# esp8266_network_speaker.net
KiCad netlist of a schematic drawn in EAGLE
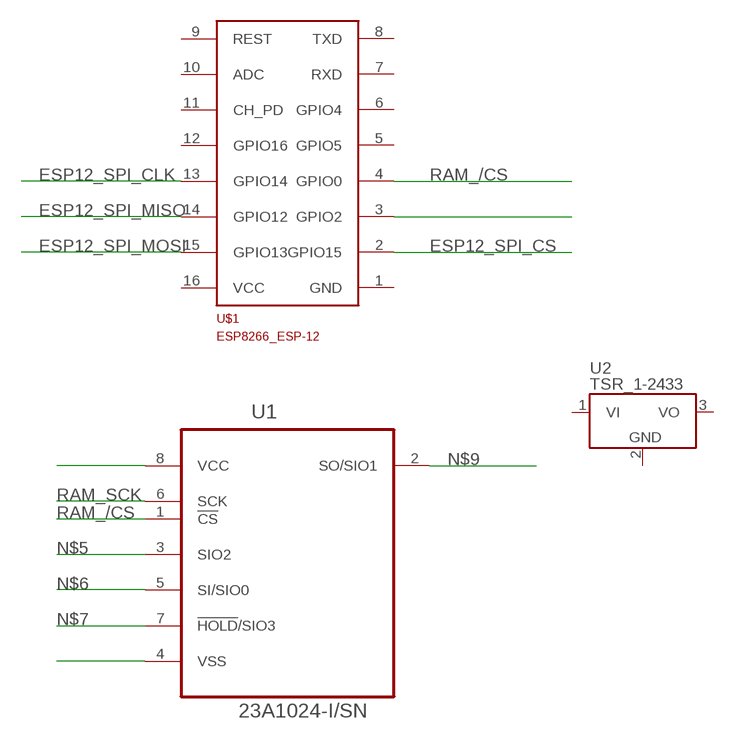
[diagram p0: schematic, sheet 1]

(export (version "E")
  (design (tool "Eeschema 10.0.6"))
  (components
    (comp (ref "U$1")
      (value "ESP8266_ESP-12")
      (footprint "eagle-import:ESP8266-ESP12")
      (libsource (lib "eagle-import") (part "ESP8266_ESP-12"))
    )
    (comp (ref "U1")
      (value "23A1024-I/SN")
      (footprint "eagle-import:SOIC127P600X175-8N")
      (libsource (lib "eagle-import") (part "23A1024-I/SN"))
    )
    (comp (ref "U2")
      (value "TSR_1-2433")
      (footprint "eagle-import:TSR-1")
      (libsource (lib "eagle-import") (part "TSR_1-2433"))
    )
  )
  (nets
    (net (code "1") (name "/ESP12_SPI_CLK") (class "Default")
      (node (ref "U$1") (pin "13") (pinfunction "GPIO14_13") (pintype "bidirectional"))
    )
    (net (code "2") (name "/ESP12_SPI_CS") (class "Default")
      (node (ref "U$1") (pin "2") (pinfunction "GPIO15_2") (pintype "bidirectional"))
    )
    (net (code "3") (name "/ESP12_SPI_MISO") (class "Default")
      (node (ref "U$1") (pin "14") (pinfunction "GPIO12_14") (pintype "bidirectional"))
    )
    (net (code "4") (name "/ESP12_SPI_MOSI") (class "Default")
      (node (ref "U$1") (pin "15") (pinfunction "GPIO13_15") (pintype "bidirectional"))
    )
    (net (code "5") (name "/GND") (class "Default")
      (node (ref "U2") (pin "2") (pinfunction "GND_2") (pintype "power_in"))
    )
    (net (code "6") (name "/N$5") (class "Default")
      (node (ref "U1") (pin "3") (pinfunction "SIO2_3") (pintype "passive"))
    )
    (net (code "7") (name "/N$6") (class "Default")
      (node (ref "U1") (pin "5") (pinfunction "SI/SIO0_5") (pintype "input"))
    )
    (net (code "8") (name "/N$7") (class "Default")
      (node (ref "U1") (pin "7") (pinfunction "~{HOLD}/SIO3_7") (pintype "passive"))
    )
    (net (code "9") (name "/N$9") (class "Default")
      (node (ref "U1") (pin "2") (pinfunction "SO/SIO1_2") (pintype "output"))
    )
    (net (code "10") (name "/RAM_SCK") (class "Default")
      (node (ref "U1") (pin "6") (pinfunction "SCK_6") (pintype "input"))
    )
    (net (code "11") (name "/RAM_{slash}CS") (class "Default")
      (node (ref "U$1") (pin "4") (pinfunction "GPIO0_4") (pintype "bidirectional"))
      (node (ref "U1") (pin "1") (pinfunction "~{CS}_1") (pintype "input"))
    )
    (net (code "12") (name "/VI") (class "Default")
      (node (ref "U2") (pin "1") (pinfunction "VI_1") (pintype "power_in"))
    )
    (net (code "13") (name "/VO") (class "Default")
      (node (ref "U2") (pin "3") (pinfunction "VO_3") (pintype "power_in"))
    )
    (net (code "14") (name "unconnected-(U$1-ADC-Pad10)") (class "Default")
      (node (ref "U$1") (pin "10") (pinfunction "ADC_10") (pintype "bidirectional"))
    )
    (net (code "15") (name "unconnected-(U$1-CH_PD-Pad11)") (class "Default")
      (node (ref "U$1") (pin "11") (pinfunction "CH_PD_11") (pintype "bidirectional"))
    )
    (net (code "16") (name "unconnected-(U$1-GND-Pad1)") (class "Default")
      (node (ref "U$1") (pin "1") (pinfunction "GND_1") (pintype "bidirectional"))
    )
    (net (code "17") (name "unconnected-(U$1-GPIO2-Pad3)") (class "Default")
      (node (ref "U$1") (pin "3") (pinfunction "GPIO2_3") (pintype "bidirectional"))
    )
    (net (code "18") (name "unconnected-(U$1-GPIO4-Pad6)") (class "Default")
      (node (ref "U$1") (pin "6") (pinfunction "GPIO4_6") (pintype "bidirectional"))
    )
    (net (code "19") (name "unconnected-(U$1-GPIO5-Pad5)") (class "Default")
      (node (ref "U$1") (pin "5") (pinfunction "GPIO5_5") (pintype "bidirectional"))
    )
    (net (code "20") (name "unconnected-(U$1-GPIO16-Pad12)") (class "Default")
      (node (ref "U$1") (pin "12") (pinfunction "GPIO16_12") (pintype "bidirectional"))
    )
    (net (code "21") (name "unconnected-(U$1-REST-Pad9)") (class "Default")
      (node (ref "U$1") (pin "9") (pinfunction "REST_9") (pintype "bidirectional"))
    )
    (net (code "22") (name "unconnected-(U$1-RXD-Pad7)") (class "Default")
      (node (ref "U$1") (pin "7") (pinfunction "RXD_7") (pintype "bidirectional"))
    )
    (net (code "23") (name "unconnected-(U$1-TXD-Pad8)") (class "Default")
      (node (ref "U$1") (pin "8") (pinfunction "TXD_8") (pintype "bidirectional"))
    )
    (net (code "24") (name "unconnected-(U$1-VCC-Pad16)") (class "Default")
      (node (ref "U$1") (pin "16") (pinfunction "VCC_16") (pintype "bidirectional"))
    )
    (net (code "25") (name "unconnected-(U1-VCC-Pad8)") (class "Default")
      (node (ref "U1") (pin "8") (pinfunction "VCC_8") (pintype "power_in"))
    )
    (net (code "26") (name "unconnected-(U1-VSS-Pad4)") (class "Default")
      (node (ref "U1") (pin "4") (pinfunction "VSS_4") (pintype "passive"))
    )
  )
)
